# alimentacion.net
KiCad netlist of a schematic drawn in Altium Designer
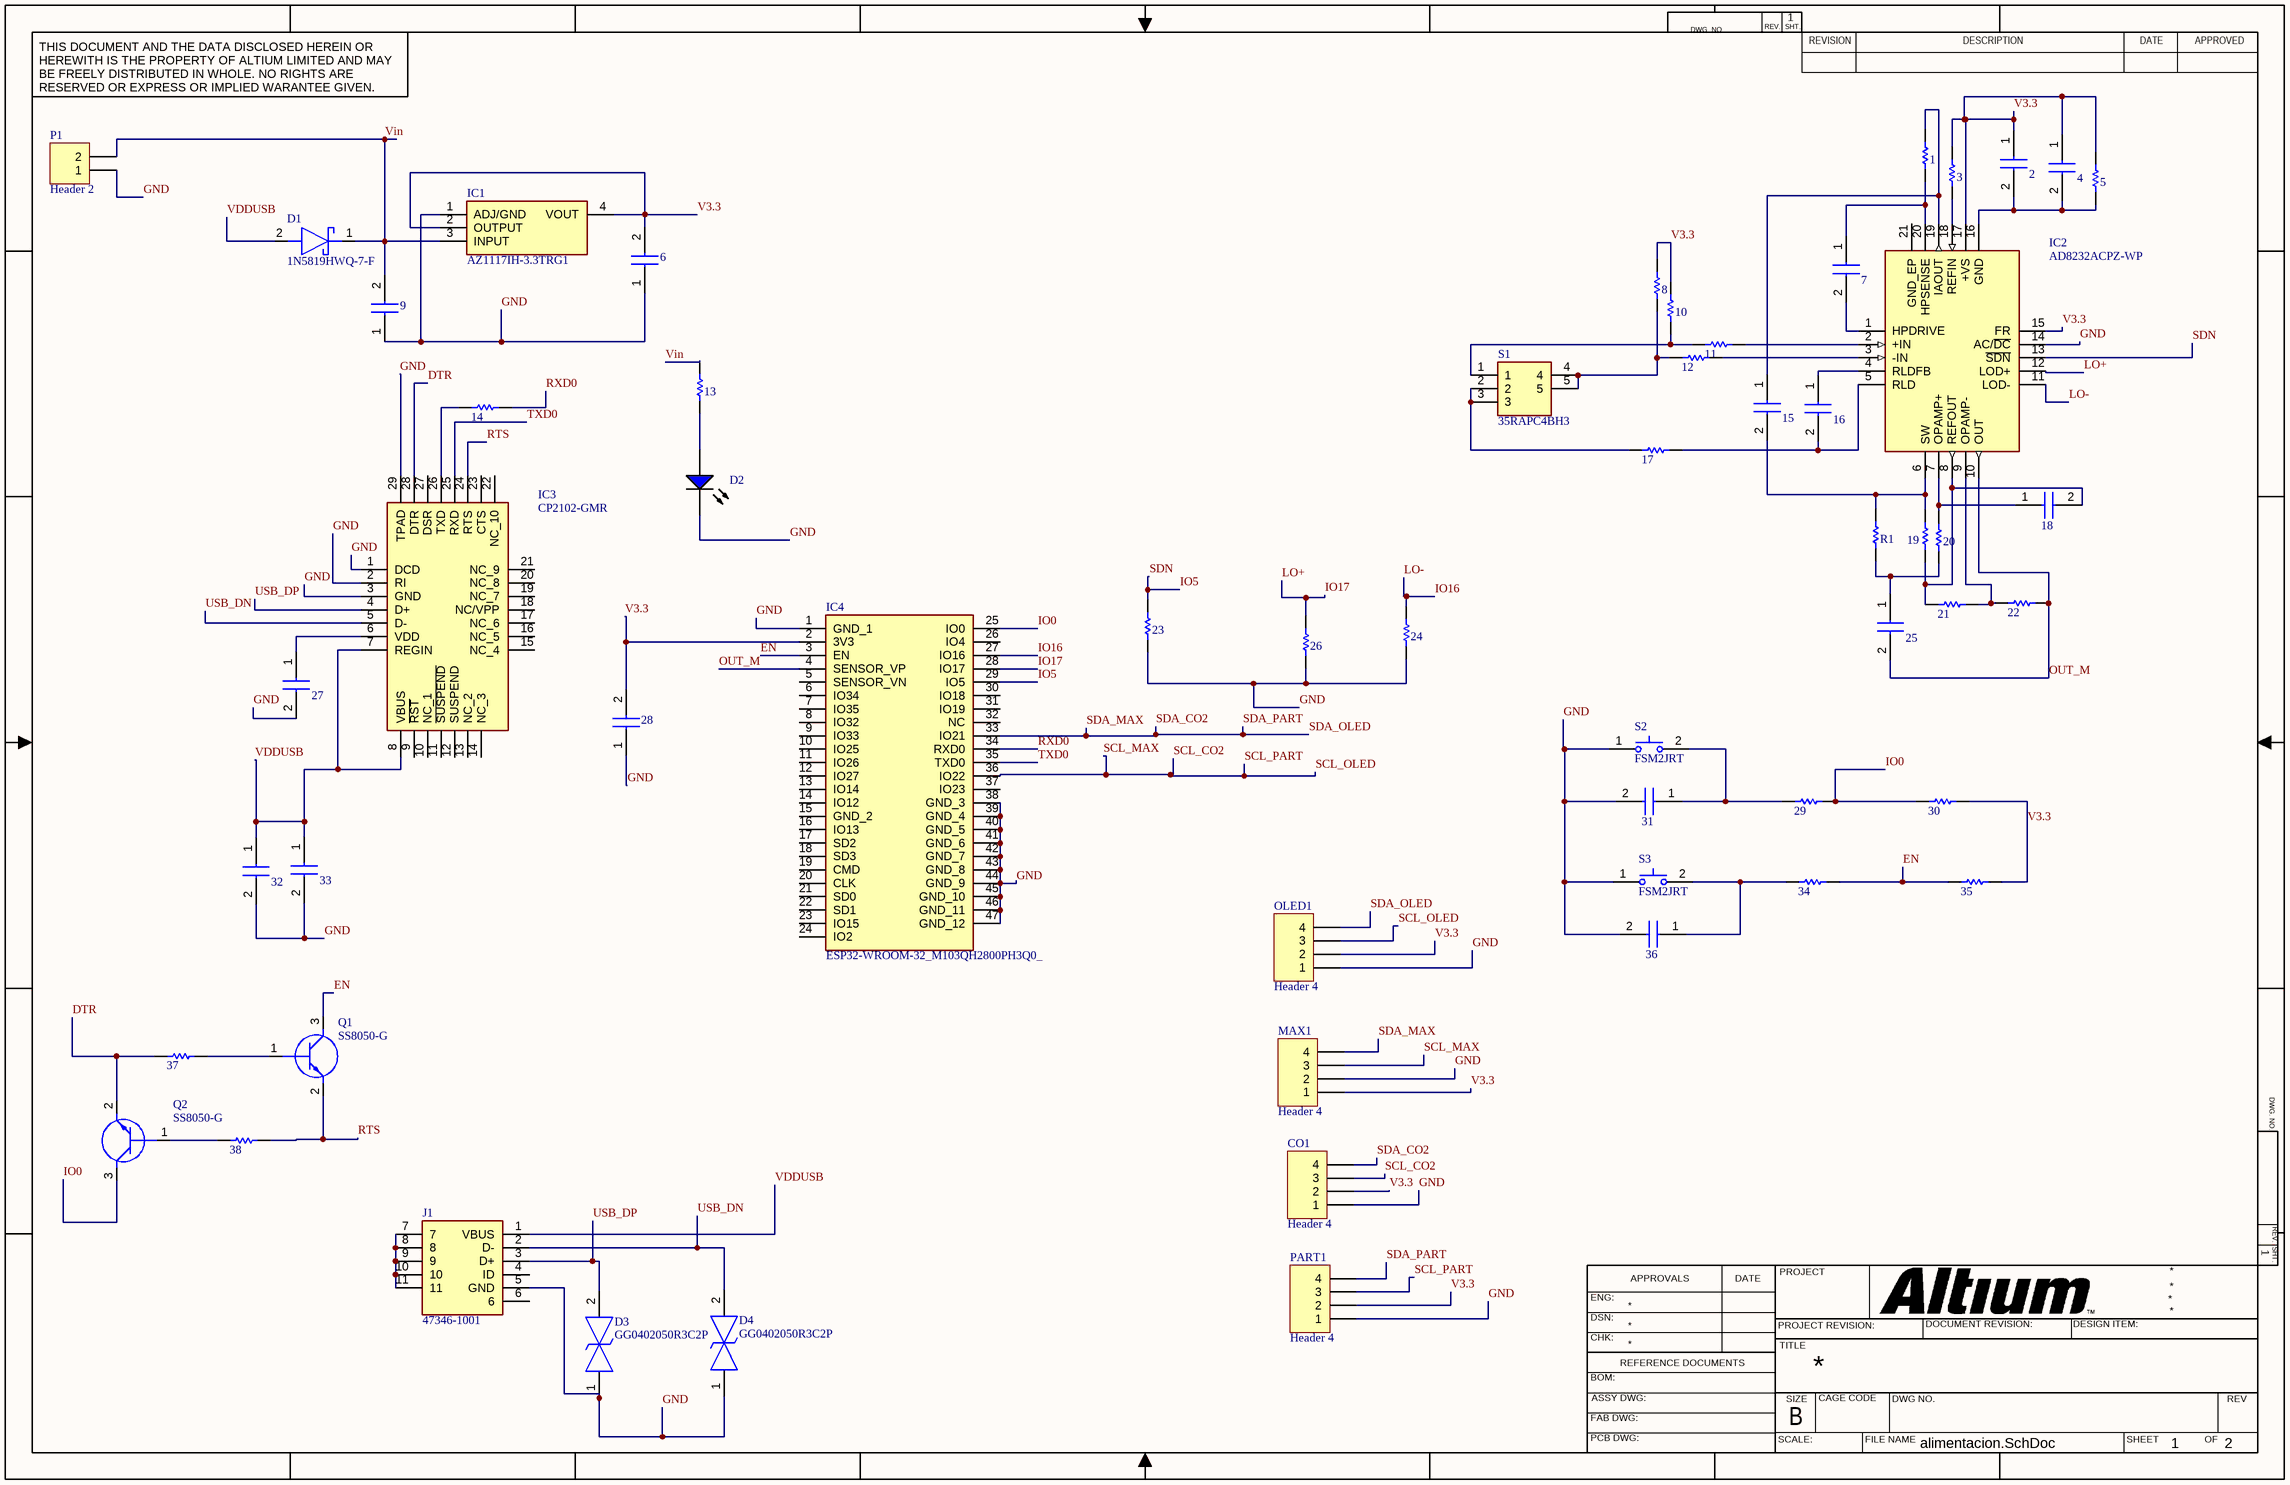
[diagram p0: alimentacion.SchDoc]

(export (version "E")
  (design (tool "Eeschema 10.0.6"))
  (components
    (comp (ref "1")
      (value "ERA3AEB1131V")
      (footprint "RESC1608X55X30ML20T20")
      (fields (field (name "MANUFACTURER") "Panasonic"))
      (libsource (lib "Altium Content Vault") (part "RES"))
    )
    (comp (ref "2")
      (value "C0603C103J5RAC")
      (footprint "SamacSys:CAPC1608X87N")
      (description "Capacitor")
      (fields (field (name "MOUSER PART NUMBER") "80-C0603C103J5RAC"))
      (libsource (lib "*") (part "C0603C103J5RAC"))
    )
    (comp (ref "3")
      (value "ERA3AEB1131V")
      (footprint "RESC1608X55X30ML20T20")
      (fields (field (name "MANUFACTURER") "Panasonic"))
      (libsource (lib "Altium Content Vault") (part "RES"))
    )
    (comp (ref "4")
      (value "C0603C103J5RAC")
      (footprint "SamacSys:CAPC1608X87N")
      (description "Capacitor")
      (fields (field (name "MOUSER PART NUMBER") "80-C0603C103J5RAC"))
      (libsource (lib "*") (part "C0603C103J5RAC"))
    )
    (comp (ref "5")
      (value "ERA3AEB1131V")
      (footprint "RESC1608X55X30ML20T20")
      (fields (field (name "MANUFACTURER") "Panasonic"))
      (libsource (lib "Altium Content Vault") (part "RES"))
    )
    (comp (ref "6")
      (value "C0603C103J5RAC")
      (footprint "SamacSys:CAPC1608X87N")
      (description "Capacitor")
      (fields (field (name "MOUSER PART NUMBER") "80-C0603C103J5RAC"))
      (libsource (lib "*") (part "C0603C103J5RAC"))
    )
    (comp (ref "7")
      (value "C0603C103J5RAC")
      (footprint "SamacSys:CAPC1608X87N")
      (description "Capacitor")
      (fields (field (name "MOUSER PART NUMBER") "80-C0603C103J5RAC"))
      (libsource (lib "*") (part "C0603C103J5RAC"))
    )
    (comp (ref "8")
      (value "ERA3AEB1131V")
      (footprint "RESC1608X55X30ML20T20")
      (fields (field (name "MANUFACTURER") "Panasonic"))
      (libsource (lib "Altium Content Vault") (part "RES"))
    )
    (comp (ref "9")
      (value "C0603C103J5RAC")
      (footprint "SamacSys:CAPC1608X87N")
      (description "Capacitor")
      (fields (field (name "MOUSER PART NUMBER") "80-C0603C103J5RAC"))
      (libsource (lib "*") (part "C0603C103J5RAC"))
    )
    (comp (ref "10")
      (value "ERA3AEB1131V")
      (footprint "RESC1608X55X30ML20T20")
      (fields (field (name "MANUFACTURER") "Panasonic"))
      (libsource (lib "Altium Content Vault") (part "RES"))
    )
    (comp (ref "11")
      (value "ERA3AEB1131V")
      (footprint "RESC1608X55X30ML20T20")
      (fields (field (name "MANUFACTURER") "Panasonic"))
      (libsource (lib "Altium Content Vault") (part "RES"))
    )
    (comp (ref "12")
      (value "ERA3AEB1131V")
      (footprint "RESC1608X55X30ML20T20")
      (fields (field (name "MANUFACTURER") "Panasonic"))
      (libsource (lib "Altium Content Vault") (part "RES"))
    )
    (comp (ref "13")
      (value "ERA3AEB1131V")
      (footprint "RESC1608X55X30ML20T20")
      (fields (field (name "MANUFACTURER") "Panasonic"))
      (libsource (lib "Altium Content Vault") (part "RES"))
    )
    (comp (ref "14")
      (value "ERA3AEB1131V")
      (footprint "RESC1608X55X30ML20T20")
      (fields (field (name "MANUFACTURER") "Panasonic"))
      (libsource (lib "Altium Content Vault") (part "RES"))
    )
    (comp (ref "15")
      (value "C0603C103J5RAC")
      (footprint "SamacSys:CAPC1608X87N")
      (description "Capacitor")
      (fields (field (name "MOUSER PART NUMBER") "80-C0603C103J5RAC"))
      (libsource (lib "*") (part "C0603C103J5RAC"))
    )
    (comp (ref "16")
      (value "C0603C103J5RAC")
      (footprint "SamacSys:CAPC1608X87N")
      (description "Capacitor")
      (fields (field (name "MOUSER PART NUMBER") "80-C0603C103J5RAC"))
      (libsource (lib "*") (part "C0603C103J5RAC"))
    )
    (comp (ref "17")
      (value "ERA3AEB1131V")
      (footprint "RESC1608X55X30ML20T20")
      (fields (field (name "MANUFACTURER") "Panasonic"))
      (libsource (lib "Altium Content Vault") (part "RES"))
    )
    (comp (ref "18")
      (value "C0603C103J5RAC")
      (footprint "SamacSys:CAPC1608X87N")
      (description "Capacitor")
      (fields (field (name "MOUSER PART NUMBER") "80-C0603C103J5RAC"))
      (libsource (lib "*") (part "C0603C103J5RAC"))
    )
    (comp (ref "19")
      (value "ERA3AEB1131V")
      (footprint "RESC1608X55X30ML20T20")
      (fields (field (name "MANUFACTURER") "Panasonic"))
      (libsource (lib "Altium Content Vault") (part "RES"))
    )
    (comp (ref "20")
      (value "ERA3AEB1131V")
      (footprint "RESC1608X55X30ML20T20")
      (fields (field (name "MANUFACTURER") "Panasonic"))
      (libsource (lib "Altium Content Vault") (part "RES"))
    )
    (comp (ref "21")
      (value "ERA3AEB1131V")
      (footprint "RESC1608X55X30ML20T20")
      (fields (field (name "MANUFACTURER") "Panasonic"))
      (libsource (lib "Altium Content Vault") (part "RES"))
    )
    (comp (ref "22")
      (value "ERA3AEB1131V")
      (footprint "RESC1608X55X30ML20T20")
      (fields (field (name "MANUFACTURER") "Panasonic"))
      (libsource (lib "Altium Content Vault") (part "RES"))
    )
    (comp (ref "23")
      (value "ERA3AEB1131V")
      (footprint "RESC1608X55X30ML20T20")
      (fields (field (name "MANUFACTURER") "Panasonic"))
      (libsource (lib "Altium Content Vault") (part "RES"))
    )
    (comp (ref "24")
      (value "ERA3AEB1131V")
      (footprint "RESC1608X55X30ML20T20")
      (fields (field (name "MANUFACTURER") "Panasonic"))
      (libsource (lib "Altium Content Vault") (part "RES"))
    )
    (comp (ref "25")
      (value "C0603C103J5RAC")
      (footprint "SamacSys:CAPC1608X87N")
      (description "Capacitor")
      (fields (field (name "MOUSER PART NUMBER") "80-C0603C103J5RAC"))
      (libsource (lib "*") (part "C0603C103J5RAC"))
    )
    (comp (ref "26")
      (value "ERA3AEB1131V")
      (footprint "RESC1608X55X30ML20T20")
      (fields (field (name "MANUFACTURER") "Panasonic"))
      (libsource (lib "Altium Content Vault") (part "RES"))
    )
    (comp (ref "27")
      (value "C0603C103J5RAC")
      (footprint "SamacSys:CAPC1608X87N")
      (description "Capacitor")
      (fields (field (name "MOUSER PART NUMBER") "80-C0603C103J5RAC"))
      (libsource (lib "*") (part "C0603C103J5RAC"))
    )
    (comp (ref "28")
      (value "C0603C103J5RAC")
      (footprint "SamacSys:CAPC1608X87N")
      (description "Capacitor")
      (fields (field (name "MOUSER PART NUMBER") "80-C0603C103J5RAC"))
      (libsource (lib "*") (part "C0603C103J5RAC"))
    )
    (comp (ref "29")
      (value "ERA3AEB1131V")
      (footprint "RESC1608X55X30ML20T20")
      (fields (field (name "MANUFACTURER") "Panasonic"))
      (libsource (lib "Altium Content Vault") (part "RES"))
    )
    (comp (ref "30")
      (value "ERA3AEB1131V")
      (footprint "RESC1608X55X30ML20T20")
      (fields (field (name "MANUFACTURER") "Panasonic"))
      (libsource (lib "Altium Content Vault") (part "RES"))
    )
    (comp (ref "31")
      (value "C0603C103J5RAC")
      (footprint "SamacSys:CAPC1608X87N")
      (description "Capacitor")
      (fields (field (name "MOUSER PART NUMBER") "80-C0603C103J5RAC"))
      (libsource (lib "*") (part "C0603C103J5RAC"))
    )
    (comp (ref "32")
      (value "C0603C103J5RAC")
      (footprint "SamacSys:CAPC1608X87N")
      (description "Capacitor")
      (fields (field (name "MOUSER PART NUMBER") "80-C0603C103J5RAC"))
      (libsource (lib "*") (part "C0603C103J5RAC"))
    )
    (comp (ref "33")
      (value "C0603C103J5RAC")
      (footprint "SamacSys:CAPC1608X87N")
      (description "Capacitor")
      (fields (field (name "MOUSER PART NUMBER") "80-C0603C103J5RAC"))
      (libsource (lib "*") (part "C0603C103J5RAC"))
    )
    (comp (ref "34")
      (value "ERA3AEB1131V")
      (footprint "RESC1608X55X30ML20T20")
      (fields (field (name "MANUFACTURER") "Panasonic"))
      (libsource (lib "Altium Content Vault") (part "RES"))
    )
    (comp (ref "35")
      (value "ERA3AEB1131V")
      (footprint "RESC1608X55X30ML20T20")
      (fields (field (name "MANUFACTURER") "Panasonic"))
      (libsource (lib "Altium Content Vault") (part "RES"))
    )
    (comp (ref "36")
      (value "C0603C103J5RAC")
      (footprint "SamacSys:CAPC1608X87N")
      (description "Capacitor")
      (fields (field (name "MOUSER PART NUMBER") "80-C0603C103J5RAC"))
      (libsource (lib "*") (part "C0603C103J5RAC"))
    )
    (comp (ref "37")
      (value "ERA3AEB1131V")
      (footprint "RESC1608X55X30ML20T20")
      (fields (field (name "MANUFACTURER") "Panasonic"))
      (libsource (lib "Altium Content Vault") (part "RES"))
    )
    (comp (ref "38")
      (value "ERA3AEB1131V")
      (footprint "RESC1608X55X30ML20T20")
      (fields (field (name "MANUFACTURER") "Panasonic"))
      (libsource (lib "Altium Content Vault") (part "RES"))
    )
    (comp (ref "CO1")
      (value "Header 4")
      (footprint "HDR1X4")
      (description "Header, 4-Pin")
      (fields (field (name "PUBLISHER") "Altium Limited"))
      (libsource (lib "Miscellaneous Connectors") (part "Header 4"))
    )
    (comp (ref "D1")
      (value "1N5819HWQ-7-F")
      (footprint "SamacSys:SOD3716X145N")
      (description "Schottky Diode")
      (fields (field (name "MOUSER PART NUMBER") "621-1N5819HWQ-7-F"))
      (libsource (lib "*") (part "1N5819HWQ-7-F"))
    )
    (comp (ref "D2")
      (value "TLMB1100-GS08")
      (footprint "VISH-TLMX1100-2_V")
      (description "Blue LED, 10 mA, 3.9 V, -40 to 100 degC, 2-Pin SMD (0603), RoHS, Tape and Reel")
      (fields (field (name "TOLERANCE") "10%"))
      (libsource (lib "Altium Content Vault") (part "LED-BLUE-AK-2"))
    )
    (comp (ref "D3")
      (value "GG0402050R3C2P")
      (footprint "SamacSys:DIONC1006X55N")
      (description "TVS Diode (Bi-directional)")
      (fields (field (name "MOUSER PART NUMBER") "581-GG0402050R3C2P"))
      (libsource (lib "*") (part "GG0402050R3C2P"))
    )
    (comp (ref "D4")
      (value "GG0402050R3C2P")
      (footprint "SamacSys:DIONC1006X55N")
      (description "TVS Diode (Bi-directional)")
      (fields (field (name "MOUSER PART NUMBER") "581-GG0402050R3C2P"))
      (libsource (lib "*") (part "GG0402050R3C2P"))
    )
    (comp (ref "IC1")
      (value "AZ1117IH-3.3TRG1")
      (footprint "SamacSys:SOT230P700X180-4N")
      (description "Integrated Circuit")
      (fields (field (name "MOUSER PART NUMBER") "621-AZ1117IH-3.3TRG1"))
      (libsource (lib "*") (part "AZ1117IH-3.3TRG1"))
    )
    (comp (ref "IC2")
      (value "AD8232ACPZ-WP")
      (footprint "SamacSys:QFN50P400X400X80-21N-D")
      (description "Integrated Circuit")
      (fields (field (name "MOUSER PART NUMBER") "584-AD8232ACPZ-WP"))
      (libsource (lib "*") (part "AD8232ACPZ-WP"))
    )
    (comp (ref "IC3")
      (value "CP2102-GMR")
      (footprint "SamacSys:QFN50P500X500X100-29N-D")
      (description "Integrated Circuit")
      (fields (field (name "MOUSER PART NUMBER") "634-CP2102-GMR"))
      (libsource (lib "*") (part "CP2102-GMR"))
    )
    (comp (ref "IC4")
      (value "ESP32-WROOM-32_M103QH2800PH3Q0_")
      (footprint "SamacSys:ESP32WROOM32M103QH2800PH3Q0")
      (description "Integrated Circuit")
      (fields
        (field (name "MANUFACTURER_PART_NUMBER") "ESP32-WROOM-32(M103QH2800PH3Q0)")
        (field (name "MOUSER PART NUMBER") "356-ESPWROOM3216MB")
      )
      (libsource (lib "*") (part "ESP32-WROOM-32_M103QH2800PH3Q0_"))
    )
    (comp (ref "J1")
      (value "47346-1001")
      (footprint "SamacSys:473461001")
      (description "Connector")
      (fields (field (name "MOUSER PART NUMBER") "538-47346-1001"))
      (libsource (lib "*") (part "47346-1001"))
    )
    (comp (ref "MAX1")
      (value "Header 4")
      (footprint "HDR1X4")
      (description "Header, 4-Pin")
      (fields (field (name "PUBLISHER") "Altium Limited"))
      (libsource (lib "Miscellaneous Connectors") (part "Header 4"))
    )
    (comp (ref "OLED1")
      (value "Header 4")
      (footprint "HDR1X4")
      (description "Header, 4-Pin")
      (fields (field (name "PUBLISHER") "Altium Limited"))
      (libsource (lib "Miscellaneous Connectors") (part "Header 4"))
    )
    (comp (ref "P1")
      (value "Header 2")
      (footprint "HDR1X2")
      (description "Header, 2-Pin")
      (fields (field (name "PUBLISHER") "Altium Limited"))
      (libsource (lib "Miscellaneous Connectors") (part "Header 2"))
    )
    (comp (ref "PART1")
      (value "Header 4")
      (footprint "HDR1X4")
      (description "Header, 4-Pin")
      (fields (field (name "PUBLISHER") "Altium Limited"))
      (libsource (lib "Miscellaneous Connectors") (part "Header 4"))
    )
    (comp (ref "Q1")
      (value "SS8050-G")
      (footprint "SamacSys:SOT95P240X115-3N")
      (description "Transistor BJT NPN")
      (fields (field (name "MOUSER PART NUMBER") "750-SS8050-G"))
      (libsource (lib "*") (part "SS8050-G"))
    )
    (comp (ref "Q2")
      (value "SS8050-G")
      (footprint "SamacSys:SOT95P240X115-3N")
      (description "Transistor BJT NPN")
      (fields (field (name "MOUSER PART NUMBER") "750-SS8050-G"))
      (libsource (lib "*") (part "SS8050-G"))
    )
    (comp (ref "R1")
      (value "ERA3AEB1131V")
      (footprint "RESC1608X55X30ML20T20")
      (fields (field (name "MANUFACTURER") "Panasonic"))
      (libsource (lib "Altium Content Vault") (part "RES"))
    )
    (comp (ref "S1")
      (value "35RAPC4BH3")
      (footprint "SamacSys:35RAPC4BH3")
      (description "Switch")
      (fields (field (name "MOUSER PART NUMBER") "502-35RAPC4BH3"))
      (libsource (lib "*") (part "35RAPC4BH3"))
    )
    (comp (ref "S2")
      (value "FSM2JRT")
      (footprint "SamacSys:FSM2JRT")
      (description "Switch (2-Pin Push)")
      (fields (field (name "MOUSER PART NUMBER") "506-FSM2JRT"))
      (libsource (lib "*") (part "FSM2JRT"))
    )
    (comp (ref "S3")
      (value "FSM2JRT")
      (footprint "SamacSys:FSM2JRT")
      (description "Switch (2-Pin Push)")
      (fields (field (name "MOUSER PART NUMBER") "506-FSM2JRT"))
      (libsource (lib "*") (part "FSM2JRT"))
    )
  )
  (nets
    (net (code "1") (name "/DTR") (class "Default")
      (node (ref "37") (pin "2") (pinfunction "2_2") (pintype "passive"))
      (node (ref "IC3") (pin "28") (pinfunction "DTR_28") (pintype "passive"))
      (node (ref "Q2") (pin "2") (pinfunction "E_2") (pintype "passive"))
    )
    (net (code "2") (name "/EN") (class "Default")
      (node (ref "34") (pin "1") (pinfunction "1_1") (pintype "passive"))
      (node (ref "35") (pin "2") (pinfunction "2_2") (pintype "passive"))
      (node (ref "IC4") (pin "3") (pinfunction "EN_3") (pintype "passive"))
      (node (ref "Q1") (pin "3") (pinfunction "C_3") (pintype "passive"))
    )
    (net (code "3") (name "/GND") (class "Default")
      (node (ref "23") (pin "2") (pinfunction "2_2") (pintype "passive"))
      (node (ref "24") (pin "2") (pinfunction "2_2") (pintype "passive"))
      (node (ref "26") (pin "2") (pinfunction "2_2") (pintype "passive"))
      (node (ref "27") (pin "2") (pinfunction "2_2") (pintype "passive"))
      (node (ref "28") (pin "1") (pinfunction "1_1") (pintype "passive"))
      (node (ref "31") (pin "2") (pinfunction "2_2") (pintype "passive"))
      (node (ref "32") (pin "2") (pinfunction "2_2") (pintype "passive"))
      (node (ref "33") (pin "2") (pinfunction "2_2") (pintype "passive"))
      (node (ref "36") (pin "2") (pinfunction "2_2") (pintype "passive"))
      (node (ref "6") (pin "1") (pinfunction "1_1") (pintype "passive"))
      (node (ref "9") (pin "1") (pinfunction "1_1") (pintype "passive"))
      (node (ref "CO1") (pin "1") (pinfunction "1_1") (pintype "passive"))
      (node (ref "D2") (pin "2") (pinfunction "K_2") (pintype "passive"))
      (node (ref "D3") (pin "1") (pinfunction "1_1") (pintype "passive"))
      (node (ref "D4") (pin "1") (pinfunction "1_1") (pintype "passive"))
      (node (ref "IC1") (pin "1") (pinfunction "ADJ/GND_1") (pintype "passive"))
      (node (ref "IC2") (pin "14") (pinfunction "AC/~{DC}_14") (pintype "passive"))
      (node (ref "IC3") (pin "1") (pinfunction "DCD_1") (pintype "passive"))
      (node (ref "IC3") (pin "2") (pinfunction "RI_2") (pintype "passive"))
      (node (ref "IC3") (pin "29") (pinfunction "TPAD_29") (pintype "passive"))
      (node (ref "IC3") (pin "3") (pinfunction "GND_3") (pintype "passive"))
      (node (ref "IC4") (pin "1") (pinfunction "GND_1_1") (pintype "passive"))
      (node (ref "IC4") (pin "38") (pinfunction "GND_3_38") (pintype "passive"))
      (node (ref "IC4") (pin "39") (pinfunction "GND_4_39") (pintype "passive"))
      (node (ref "IC4") (pin "40") (pinfunction "GND_5_40") (pintype "passive"))
      (node (ref "IC4") (pin "41") (pinfunction "GND_6_41") (pintype "passive"))
      (node (ref "IC4") (pin "42") (pinfunction "GND_7_42") (pintype "passive"))
      (node (ref "IC4") (pin "43") (pinfunction "GND_8_43") (pintype "passive"))
      (node (ref "IC4") (pin "44") (pinfunction "GND_9_44") (pintype "passive"))
      (node (ref "IC4") (pin "45") (pinfunction "GND_10_45") (pintype "passive"))
      (node (ref "IC4") (pin "46") (pinfunction "GND_11_46") (pintype "passive"))
      (node (ref "IC4") (pin "47") (pinfunction "GND_12_47") (pintype "passive"))
      (node (ref "J1") (pin "5") (pinfunction "GND_5") (pintype "passive"))
      (node (ref "MAX1") (pin "2") (pinfunction "2_2") (pintype "passive"))
      (node (ref "OLED1") (pin "1") (pinfunction "1_1") (pintype "passive"))
      (node (ref "P1") (pin "1") (pinfunction "1_1") (pintype "passive"))
      (node (ref "PART1") (pin "1") (pinfunction "1_1") (pintype "passive"))
      (node (ref "S2") (pin "1") (pinfunction "COM_1") (pintype "passive"))
      (node (ref "S3") (pin "1") (pinfunction "COM_1") (pintype "passive"))
    )
    (net (code "4") (name "/IO0") (class "Default")
      (node (ref "29") (pin "1") (pinfunction "1_1") (pintype "passive"))
      (node (ref "30") (pin "2") (pinfunction "2_2") (pintype "passive"))
      (node (ref "IC4") (pin "25") (pinfunction "IO0_25") (pintype "passive"))
      (node (ref "Q2") (pin "3") (pinfunction "C_3") (pintype "passive"))
    )
    (net (code "5") (name "/IO5") (class "Default")
      (node (ref "23") (pin "1") (pinfunction "1_1") (pintype "passive"))
      (node (ref "IC2") (pin "13") (pinfunction "~{SDN}_13") (pintype "passive"))
      (node (ref "IC4") (pin "29") (pinfunction "IO5_29") (pintype "passive"))
    )
    (net (code "6") (name "/IO16") (class "Default")
      (node (ref "24") (pin "1") (pinfunction "1_1") (pintype "passive"))
      (node (ref "IC2") (pin "11") (pinfunction "LOD-_11") (pintype "passive"))
      (node (ref "IC4") (pin "27") (pinfunction "IO16_27") (pintype "passive"))
    )
    (net (code "7") (name "/IO17") (class "Default")
      (node (ref "26") (pin "1") (pinfunction "1_1") (pintype "passive"))
      (node (ref "IC2") (pin "12") (pinfunction "LOD+_12") (pintype "passive"))
      (node (ref "IC4") (pin "28") (pinfunction "IO17_28") (pintype "passive"))
    )
    (net (code "8") (name "/OUT_M") (class "Default")
      (node (ref "22") (pin "1") (pinfunction "1_1") (pintype "passive"))
      (node (ref "25") (pin "2") (pinfunction "2_2") (pintype "passive"))
      (node (ref "IC2") (pin "10") (pinfunction "OUT_10") (pintype "output"))
      (node (ref "IC4") (pin "4") (pinfunction "SENSOR_VP_4") (pintype "passive"))
    )
    (net (code "9") (name "/RTS") (class "Default")
      (node (ref "38") (pin "1") (pinfunction "1_1") (pintype "passive"))
      (node (ref "IC3") (pin "24") (pinfunction "RTS_24") (pintype "passive"))
      (node (ref "Q1") (pin "2") (pinfunction "E_2") (pintype "passive"))
    )
    (net (code "10") (name "/RXD0") (class "Default")
      (node (ref "14") (pin "1") (pinfunction "1_1") (pintype "passive"))
      (node (ref "IC4") (pin "34") (pinfunction "RXD0_34") (pintype "passive"))
    )
    (net (code "11") (name "/SCL_CO2") (class "Default")
      (node (ref "CO1") (pin "3") (pinfunction "3_3") (pintype "passive"))
      (node (ref "IC4") (pin "36") (pinfunction "IO22_36") (pintype "passive"))
      (node (ref "MAX1") (pin "3") (pinfunction "3_3") (pintype "passive"))
      (node (ref "OLED1") (pin "3") (pinfunction "3_3") (pintype "passive"))
      (node (ref "PART1") (pin "3") (pinfunction "3_3") (pintype "passive"))
    )
    (net (code "12") (name "/SDA_CO2") (class "Default")
      (node (ref "CO1") (pin "4") (pinfunction "4_4") (pintype "passive"))
      (node (ref "IC4") (pin "33") (pinfunction "IO21_33") (pintype "passive"))
      (node (ref "MAX1") (pin "4") (pinfunction "4_4") (pintype "passive"))
      (node (ref "OLED1") (pin "4") (pinfunction "4_4") (pintype "passive"))
      (node (ref "PART1") (pin "4") (pinfunction "4_4") (pintype "passive"))
    )
    (net (code "13") (name "/TXD0") (class "Default")
      (node (ref "IC3") (pin "25") (pinfunction "RXD_25") (pintype "passive"))
      (node (ref "IC4") (pin "35") (pinfunction "TXD0_35") (pintype "passive"))
    )
    (net (code "14") (name "/USB_DN") (class "Default")
      (node (ref "D4") (pin "2") (pinfunction "2_2") (pintype "passive"))
      (node (ref "IC3") (pin "5") (pinfunction "D-_5") (pintype "passive"))
      (node (ref "J1") (pin "2") (pinfunction "D-_2") (pintype "passive"))
    )
    (net (code "15") (name "/USB_DP") (class "Default")
      (node (ref "D3") (pin "2") (pinfunction "2_2") (pintype "passive"))
      (node (ref "IC3") (pin "4") (pinfunction "D+_4") (pintype "passive"))
      (node (ref "J1") (pin "3") (pinfunction "D+_3") (pintype "passive"))
    )
    (net (code "16") (name "/V3.3") (class "Default")
      (node (ref "10") (pin "1") (pinfunction "1_1") (pintype "passive"))
      (node (ref "2") (pin "1") (pinfunction "1_1") (pintype "passive"))
      (node (ref "28") (pin "2") (pinfunction "2_2") (pintype "passive"))
      (node (ref "3") (pin "1") (pinfunction "1_1") (pintype "passive"))
      (node (ref "30") (pin "1") (pinfunction "1_1") (pintype "passive"))
      (node (ref "35") (pin "1") (pinfunction "1_1") (pintype "passive"))
      (node (ref "4") (pin "1") (pinfunction "1_1") (pintype "passive"))
      (node (ref "5") (pin "1") (pinfunction "1_1") (pintype "passive"))
      (node (ref "6") (pin "2") (pinfunction "2_2") (pintype "passive"))
      (node (ref "8") (pin "1") (pinfunction "1_1") (pintype "passive"))
      (node (ref "CO1") (pin "2") (pinfunction "2_2") (pintype "passive"))
      (node (ref "IC1") (pin "2") (pinfunction "OUTPUT_2") (pintype "passive"))
      (node (ref "IC1") (pin "4") (pinfunction "VOUT_4") (pintype "passive"))
      (node (ref "IC2") (pin "15") (pinfunction "FR_15") (pintype "passive"))
      (node (ref "IC2") (pin "17") (pinfunction "+VS_17") (pintype "passive"))
      (node (ref "IC4") (pin "2") (pinfunction "3V3_2") (pintype "passive"))
      (node (ref "MAX1") (pin "1") (pinfunction "1_1") (pintype "passive"))
      (node (ref "OLED1") (pin "2") (pinfunction "2_2") (pintype "passive"))
      (node (ref "PART1") (pin "2") (pinfunction "2_2") (pintype "passive"))
    )
    (net (code "17") (name "/VDDUSB") (class "Default")
      (node (ref "32") (pin "1") (pinfunction "1_1") (pintype "passive"))
      (node (ref "33") (pin "1") (pinfunction "1_1") (pintype "passive"))
      (node (ref "D1") (pin "2") (pinfunction "A_2") (pintype "passive"))
      (node (ref "IC3") (pin "7") (pinfunction "REGIN_7") (pintype "passive"))
      (node (ref "IC3") (pin "8") (pinfunction "VBUS_8") (pintype "passive"))
      (node (ref "J1") (pin "1") (pinfunction "VBUS_1") (pintype "passive"))
    )
    (net (code "18") (name "/Vin") (class "Default")
      (node (ref "13") (pin "2") (pinfunction "2_2") (pintype "passive"))
      (node (ref "9") (pin "2") (pinfunction "2_2") (pintype "passive"))
      (node (ref "D1") (pin "1") (pinfunction "K_1") (pintype "passive"))
      (node (ref "IC1") (pin "3") (pinfunction "INPUT_3") (pintype "passive"))
      (node (ref "P1") (pin "2") (pinfunction "2_2") (pintype "passive"))
    )
    (net (code "19") (name "Net-(10-Pad2)") (class "Default")
      (node (ref "10") (pin "2") (pinfunction "2_2") (pintype "passive"))
      (node (ref "11") (pin "2") (pinfunction "2_2") (pintype "passive"))
      (node (ref "S1") (pin "1") (pinfunction "1_1") (pintype "passive"))
    )
    (net (code "20") (name "Net-(12-Pad2)") (class "Default")
      (node (ref "12") (pin "2") (pinfunction "2_2") (pintype "passive"))
      (node (ref "8") (pin "2") (pinfunction "2_2") (pintype "passive"))
      (node (ref "S1") (pin "4") (pinfunction "4_4") (pintype "passive"))
      (node (ref "S1") (pin "5") (pinfunction "5_5") (pintype "passive"))
    )
    (net (code "21") (name "Net-(17-Pad1)") (class "Default")
      (node (ref "17") (pin "1") (pinfunction "1_1") (pintype "passive"))
      (node (ref "S1") (pin "2") (pinfunction "2_2") (pintype "passive"))
      (node (ref "S1") (pin "3") (pinfunction "3_3") (pintype "passive"))
    )
    (net (code "22") (name "Net-(20-Pad2)") (class "Default")
      (node (ref "20") (pin "2") (pinfunction "2_2") (pintype "passive"))
      (node (ref "25") (pin "1") (pinfunction "1_1") (pintype "passive"))
      (node (ref "R1") (pin "2") (pinfunction "2_2") (pintype "passive"))
    )
    (net (code "23") (name "Net-(D2-A)") (class "Default")
      (node (ref "13") (pin "1") (pinfunction "1_1") (pintype "passive"))
      (node (ref "D2") (pin "1") (pinfunction "A_1") (pintype "passive"))
    )
    (net (code "24") (name "Net-(IC2-+IN)") (class "Default")
      (node (ref "11") (pin "1") (pinfunction "1_1") (pintype "passive"))
      (node (ref "IC2") (pin "2") (pinfunction "+IN_2") (pintype "input"))
    )
    (net (code "25") (name "Net-(IC2--IN)") (class "Default")
      (node (ref "12") (pin "1") (pinfunction "1_1") (pintype "passive"))
      (node (ref "IC2") (pin "3") (pinfunction "-IN_3") (pintype "input"))
    )
    (net (code "26") (name "Net-(IC2-GND)") (class "Default")
      (node (ref "2") (pin "2") (pinfunction "2_2") (pintype "passive"))
      (node (ref "4") (pin "2") (pinfunction "2_2") (pintype "passive"))
      (node (ref "5") (pin "2") (pinfunction "2_2") (pintype "passive"))
      (node (ref "IC2") (pin "16") (pinfunction "GND_16") (pintype "power_in"))
    )
    (net (code "27") (name "Net-(IC2-HPDRIVE)") (class "Default")
      (node (ref "7") (pin "2") (pinfunction "2_2") (pintype "passive"))
      (node (ref "IC2") (pin "1") (pinfunction "HPDRIVE_1") (pintype "passive"))
    )
    (net (code "28") (name "Net-(IC2-HPSENSE)") (class "Default")
      (node (ref "1") (pin "2") (pinfunction "2_2") (pintype "passive"))
      (node (ref "7") (pin "1") (pinfunction "1_1") (pintype "passive"))
      (node (ref "IC2") (pin "20") (pinfunction "HPSENSE_20") (pintype "passive"))
    )
    (net (code "29") (name "Net-(IC2-IAOUT)") (class "Default")
      (node (ref "1") (pin "1") (pinfunction "1_1") (pintype "passive"))
      (node (ref "15") (pin "1") (pinfunction "1_1") (pintype "passive"))
      (node (ref "IC2") (pin "19") (pinfunction "IAOUT_19") (pintype "output"))
    )
    (net (code "30") (name "Net-(IC2-OPAMP+)") (class "Default")
      (node (ref "18") (pin "1") (pinfunction "1_1") (pintype "passive"))
      (node (ref "20") (pin "1") (pinfunction "1_1") (pintype "passive"))
      (node (ref "IC2") (pin "7") (pinfunction "OPAMP+_7") (pintype "passive"))
    )
    (net (code "31") (name "Net-(IC2-OPAMP-)") (class "Default")
      (node (ref "21") (pin "2") (pinfunction "2_2") (pintype "passive"))
      (node (ref "22") (pin "2") (pinfunction "2_2") (pintype "passive"))
      (node (ref "IC2") (pin "9") (pinfunction "OPAMP-_9") (pintype "passive"))
    )
    (net (code "32") (name "Net-(IC2-REFIN)") (class "Default")
      (node (ref "3") (pin "2") (pinfunction "2_2") (pintype "passive"))
      (node (ref "IC2") (pin "18") (pinfunction "REFIN_18") (pintype "input"))
    )
    (net (code "33") (name "Net-(IC2-REFOUT)") (class "Default")
      (node (ref "18") (pin "2") (pinfunction "2_2") (pintype "passive"))
      (node (ref "19") (pin "2") (pinfunction "2_2") (pintype "passive"))
      (node (ref "21") (pin "1") (pinfunction "1_1") (pintype "passive"))
      (node (ref "IC2") (pin "8") (pinfunction "REFOUT_8") (pintype "output"))
    )
    (net (code "34") (name "Net-(IC2-RLD)") (class "Default")
      (node (ref "16") (pin "2") (pinfunction "2_2") (pintype "passive"))
      (node (ref "17") (pin "2") (pinfunction "2_2") (pintype "passive"))
      (node (ref "IC2") (pin "5") (pinfunction "RLD_5") (pintype "passive"))
    )
    (net (code "35") (name "Net-(IC2-RLDFB)") (class "Default")
      (node (ref "16") (pin "1") (pinfunction "1_1") (pintype "passive"))
      (node (ref "IC2") (pin "4") (pinfunction "RLDFB_4") (pintype "passive"))
    )
    (net (code "36") (name "Net-(IC2-SW)") (class "Default")
      (node (ref "15") (pin "2") (pinfunction "2_2") (pintype "passive"))
      (node (ref "19") (pin "1") (pinfunction "1_1") (pintype "passive"))
      (node (ref "IC2") (pin "6") (pinfunction "SW_6") (pintype "passive"))
      (node (ref "R1") (pin "1") (pinfunction "1_1") (pintype "passive"))
    )
    (net (code "37") (name "Net-(IC3-TXD)") (class "Default")
      (node (ref "14") (pin "2") (pinfunction "2_2") (pintype "passive"))
      (node (ref "IC3") (pin "26") (pinfunction "TXD_26") (pintype "passive"))
    )
    (net (code "38") (name "Net-(IC3-VDD)") (class "Default")
      (node (ref "27") (pin "1") (pinfunction "1_1") (pintype "passive"))
      (node (ref "IC3") (pin "6") (pinfunction "VDD_6") (pintype "passive"))
    )
    (net (code "39") (name "Net-(J1-Pad10)") (class "Default")
      (node (ref "J1") (pin "10") (pinfunction "10_10") (pintype "passive"))
      (node (ref "J1") (pin "11") (pinfunction "11_11") (pintype "passive"))
      (node (ref "J1") (pin "7") (pinfunction "7_7") (pintype "passive"))
      (node (ref "J1") (pin "8") (pinfunction "8_8") (pintype "passive"))
      (node (ref "J1") (pin "9") (pinfunction "9_9") (pintype "passive"))
    )
    (net (code "40") (name "Net-(Q1-B)") (class "Default")
      (node (ref "37") (pin "1") (pinfunction "1_1") (pintype "passive"))
      (node (ref "Q1") (pin "1") (pinfunction "B_1") (pintype "passive"))
    )
    (net (code "41") (name "Net-(Q2-B)") (class "Default")
      (node (ref "38") (pin "2") (pinfunction "2_2") (pintype "passive"))
      (node (ref "Q2") (pin "1") (pinfunction "B_1") (pintype "passive"))
    )
    (net (code "42") (name "Net-(S2-NO)") (class "Default")
      (node (ref "29") (pin "2") (pinfunction "2_2") (pintype "passive"))
      (node (ref "31") (pin "1") (pinfunction "1_1") (pintype "passive"))
      (node (ref "S2") (pin "2") (pinfunction "NO_2") (pintype "passive"))
    )
    (net (code "43") (name "Net-(S3-NO)") (class "Default")
      (node (ref "34") (pin "2") (pinfunction "2_2") (pintype "passive"))
      (node (ref "36") (pin "1") (pinfunction "1_1") (pintype "passive"))
      (node (ref "S3") (pin "2") (pinfunction "NO_2") (pintype "passive"))
    )
    (net (code "44") (name "unconnected-(IC2-GND_EP-Pad21)") (class "Default")
      (node (ref "IC2") (pin "21") (pinfunction "GND_EP_21") (pintype "power_in"))
    )
    (net (code "45") (name "unconnected-(IC3-CTS-Pad23)") (class "Default")
      (node (ref "IC3") (pin "23") (pinfunction "CTS_23") (pintype "passive"))
    )
    (net (code "46") (name "unconnected-(IC3-DSR-Pad27)") (class "Default")
      (node (ref "IC3") (pin "27") (pinfunction "DSR_27") (pintype "passive"))
    )
    (net (code "47") (name "unconnected-(IC3-NC_1-Pad10)") (class "Default")
      (node (ref "IC3") (pin "10") (pinfunction "NC_1_10") (pintype "passive"))
    )
    (net (code "48") (name "unconnected-(IC3-NC_2-Pad13)") (class "Default")
      (node (ref "IC3") (pin "13") (pinfunction "NC_2_13") (pintype "passive"))
    )
    (net (code "49") (name "unconnected-(IC3-NC_3-Pad14)") (class "Default")
      (node (ref "IC3") (pin "14") (pinfunction "NC_3_14") (pintype "passive"))
    )
    (net (code "50") (name "unconnected-(IC3-NC_4-Pad15)") (class "Default")
      (node (ref "IC3") (pin "15") (pinfunction "NC_4_15") (pintype "passive"))
    )
    (net (code "51") (name "unconnected-(IC3-NC_5-Pad16)") (class "Default")
      (node (ref "IC3") (pin "16") (pinfunction "NC_5_16") (pintype "passive"))
    )
    (net (code "52") (name "unconnected-(IC3-NC_6-Pad17)") (class "Default")
      (node (ref "IC3") (pin "17") (pinfunction "NC_6_17") (pintype "passive"))
    )
    (net (code "53") (name "unconnected-(IC3-NC_7-Pad19)") (class "Default")
      (node (ref "IC3") (pin "19") (pinfunction "NC_7_19") (pintype "passive"))
    )
    (net (code "54") (name "unconnected-(IC3-NC_8-Pad20)") (class "Default")
      (node (ref "IC3") (pin "20") (pinfunction "NC_8_20") (pintype "passive"))
    )
    (net (code "55") (name "unconnected-(IC3-NC_9-Pad21)") (class "Default")
      (node (ref "IC3") (pin "21") (pinfunction "NC_9_21") (pintype "passive"))
    )
    (net (code "56") (name "unconnected-(IC3-NC_10-Pad22)") (class "Default")
      (node (ref "IC3") (pin "22") (pinfunction "NC_10_22") (pintype "passive"))
    )
    (net (code "57") (name "unconnected-(IC3-NC{slash}VPP-Pad18)") (class "Default")
      (node (ref "IC3") (pin "18") (pinfunction "NC/VPP_18") (pintype "passive"))
    )
    (net (code "58") (name "unconnected-(IC3-SUSPEND-Pad12)") (class "Default")
      (node (ref "IC3") (pin "12") (pinfunction "SUSPEND_12") (pintype "passive"))
    )
    (net (code "59") (name "unconnected-(IC3-~{RST}-Pad9)") (class "Default")
      (node (ref "IC3") (pin "9") (pinfunction "~{RST}_9") (pintype "passive"))
    )
    (net (code "60") (name "unconnected-(IC3-~{SUSPEND}-Pad11)") (class "Default")
      (node (ref "IC3") (pin "11") (pinfunction "~{SUSPEND}_11") (pintype "passive"))
    )
    (net (code "61") (name "unconnected-(IC4-CLK-Pad20)") (class "Default")
      (node (ref "IC4") (pin "20") (pinfunction "CLK_20") (pintype "passive"))
    )
    (net (code "62") (name "unconnected-(IC4-CMD-Pad19)") (class "Default")
      (node (ref "IC4") (pin "19") (pinfunction "CMD_19") (pintype "passive"))
    )
    (net (code "63") (name "unconnected-(IC4-GND_2-Pad15)") (class "Default")
      (node (ref "IC4") (pin "15") (pinfunction "GND_2_15") (pintype "passive"))
    )
    (net (code "64") (name "unconnected-(IC4-IO2-Pad24)") (class "Default")
      (node (ref "IC4") (pin "24") (pinfunction "IO2_24") (pintype "passive"))
    )
    (net (code "65") (name "unconnected-(IC4-IO4-Pad26)") (class "Default")
      (node (ref "IC4") (pin "26") (pinfunction "IO4_26") (pintype "passive"))
    )
    (net (code "66") (name "unconnected-(IC4-IO12-Pad14)") (class "Default")
      (node (ref "IC4") (pin "14") (pinfunction "IO12_14") (pintype "passive"))
    )
    (net (code "67") (name "unconnected-(IC4-IO13-Pad16)") (class "Default")
      (node (ref "IC4") (pin "16") (pinfunction "IO13_16") (pintype "passive"))
    )
    (net (code "68") (name "unconnected-(IC4-IO14-Pad13)") (class "Default")
      (node (ref "IC4") (pin "13") (pinfunction "IO14_13") (pintype "passive"))
    )
    (net (code "69") (name "unconnected-(IC4-IO15-Pad23)") (class "Default")
      (node (ref "IC4") (pin "23") (pinfunction "IO15_23") (pintype "passive"))
    )
    (net (code "70") (name "unconnected-(IC4-IO18-Pad30)") (class "Default")
      (node (ref "IC4") (pin "30") (pinfunction "IO18_30") (pintype "passive"))
    )
    (net (code "71") (name "unconnected-(IC4-IO19-Pad31)") (class "Default")
      (node (ref "IC4") (pin "31") (pinfunction "IO19_31") (pintype "passive"))
    )
    (net (code "72") (name "unconnected-(IC4-IO23-Pad37)") (class "Default")
      (node (ref "IC4") (pin "37") (pinfunction "IO23_37") (pintype "passive"))
    )
    (net (code "73") (name "unconnected-(IC4-IO25-Pad10)") (class "Default")
      (node (ref "IC4") (pin "10") (pinfunction "IO25_10") (pintype "passive"))
    )
    (net (code "74") (name "unconnected-(IC4-IO26-Pad11)") (class "Default")
      (node (ref "IC4") (pin "11") (pinfunction "IO26_11") (pintype "passive"))
    )
    (net (code "75") (name "unconnected-(IC4-IO27-Pad12)") (class "Default")
      (node (ref "IC4") (pin "12") (pinfunction "IO27_12") (pintype "passive"))
    )
    (net (code "76") (name "unconnected-(IC4-IO32-Pad8)") (class "Default")
      (node (ref "IC4") (pin "8") (pinfunction "IO32_8") (pintype "passive"))
    )
    (net (code "77") (name "unconnected-(IC4-IO33-Pad9)") (class "Default")
      (node (ref "IC4") (pin "9") (pinfunction "IO33_9") (pintype "passive"))
    )
    (net (code "78") (name "unconnected-(IC4-IO34-Pad6)") (class "Default")
      (node (ref "IC4") (pin "6") (pinfunction "IO34_6") (pintype "passive"))
    )
    (net (code "79") (name "unconnected-(IC4-IO35-Pad7)") (class "Default")
      (node (ref "IC4") (pin "7") (pinfunction "IO35_7") (pintype "passive"))
    )
    (net (code "80") (name "unconnected-(IC4-NC-Pad32)") (class "Default")
      (node (ref "IC4") (pin "32") (pinfunction "NC_32") (pintype "passive"))
    )
    (net (code "81") (name "unconnected-(IC4-SD0-Pad21)") (class "Default")
      (node (ref "IC4") (pin "21") (pinfunction "SD0_21") (pintype "passive"))
    )
    (net (code "82") (name "unconnected-(IC4-SD1-Pad22)") (class "Default")
      (node (ref "IC4") (pin "22") (pinfunction "SD1_22") (pintype "passive"))
    )
    (net (code "83") (name "unconnected-(IC4-SD2-Pad17)") (class "Default")
      (node (ref "IC4") (pin "17") (pinfunction "SD2_17") (pintype "passive"))
    )
    (net (code "84") (name "unconnected-(IC4-SD3-Pad18)") (class "Default")
      (node (ref "IC4") (pin "18") (pinfunction "SD3_18") (pintype "passive"))
    )
    (net (code "85") (name "unconnected-(IC4-SENSOR_VN-Pad5)") (class "Default")
      (node (ref "IC4") (pin "5") (pinfunction "SENSOR_VN_5") (pintype "passive"))
    )
    (net (code "86") (name "unconnected-(J1-ID-Pad4)") (class "Default")
      (node (ref "J1") (pin "4") (pinfunction "ID_4") (pintype "passive"))
    )
    (net (code "87") (name "unconnected-(J1-Pad6)") (class "Default")
      (node (ref "J1") (pin "6") (pinfunction "6_6") (pintype "passive"))
    )
  )
)
